# Sen.net
KiCad netlist of a schematic drawn in EAGLE
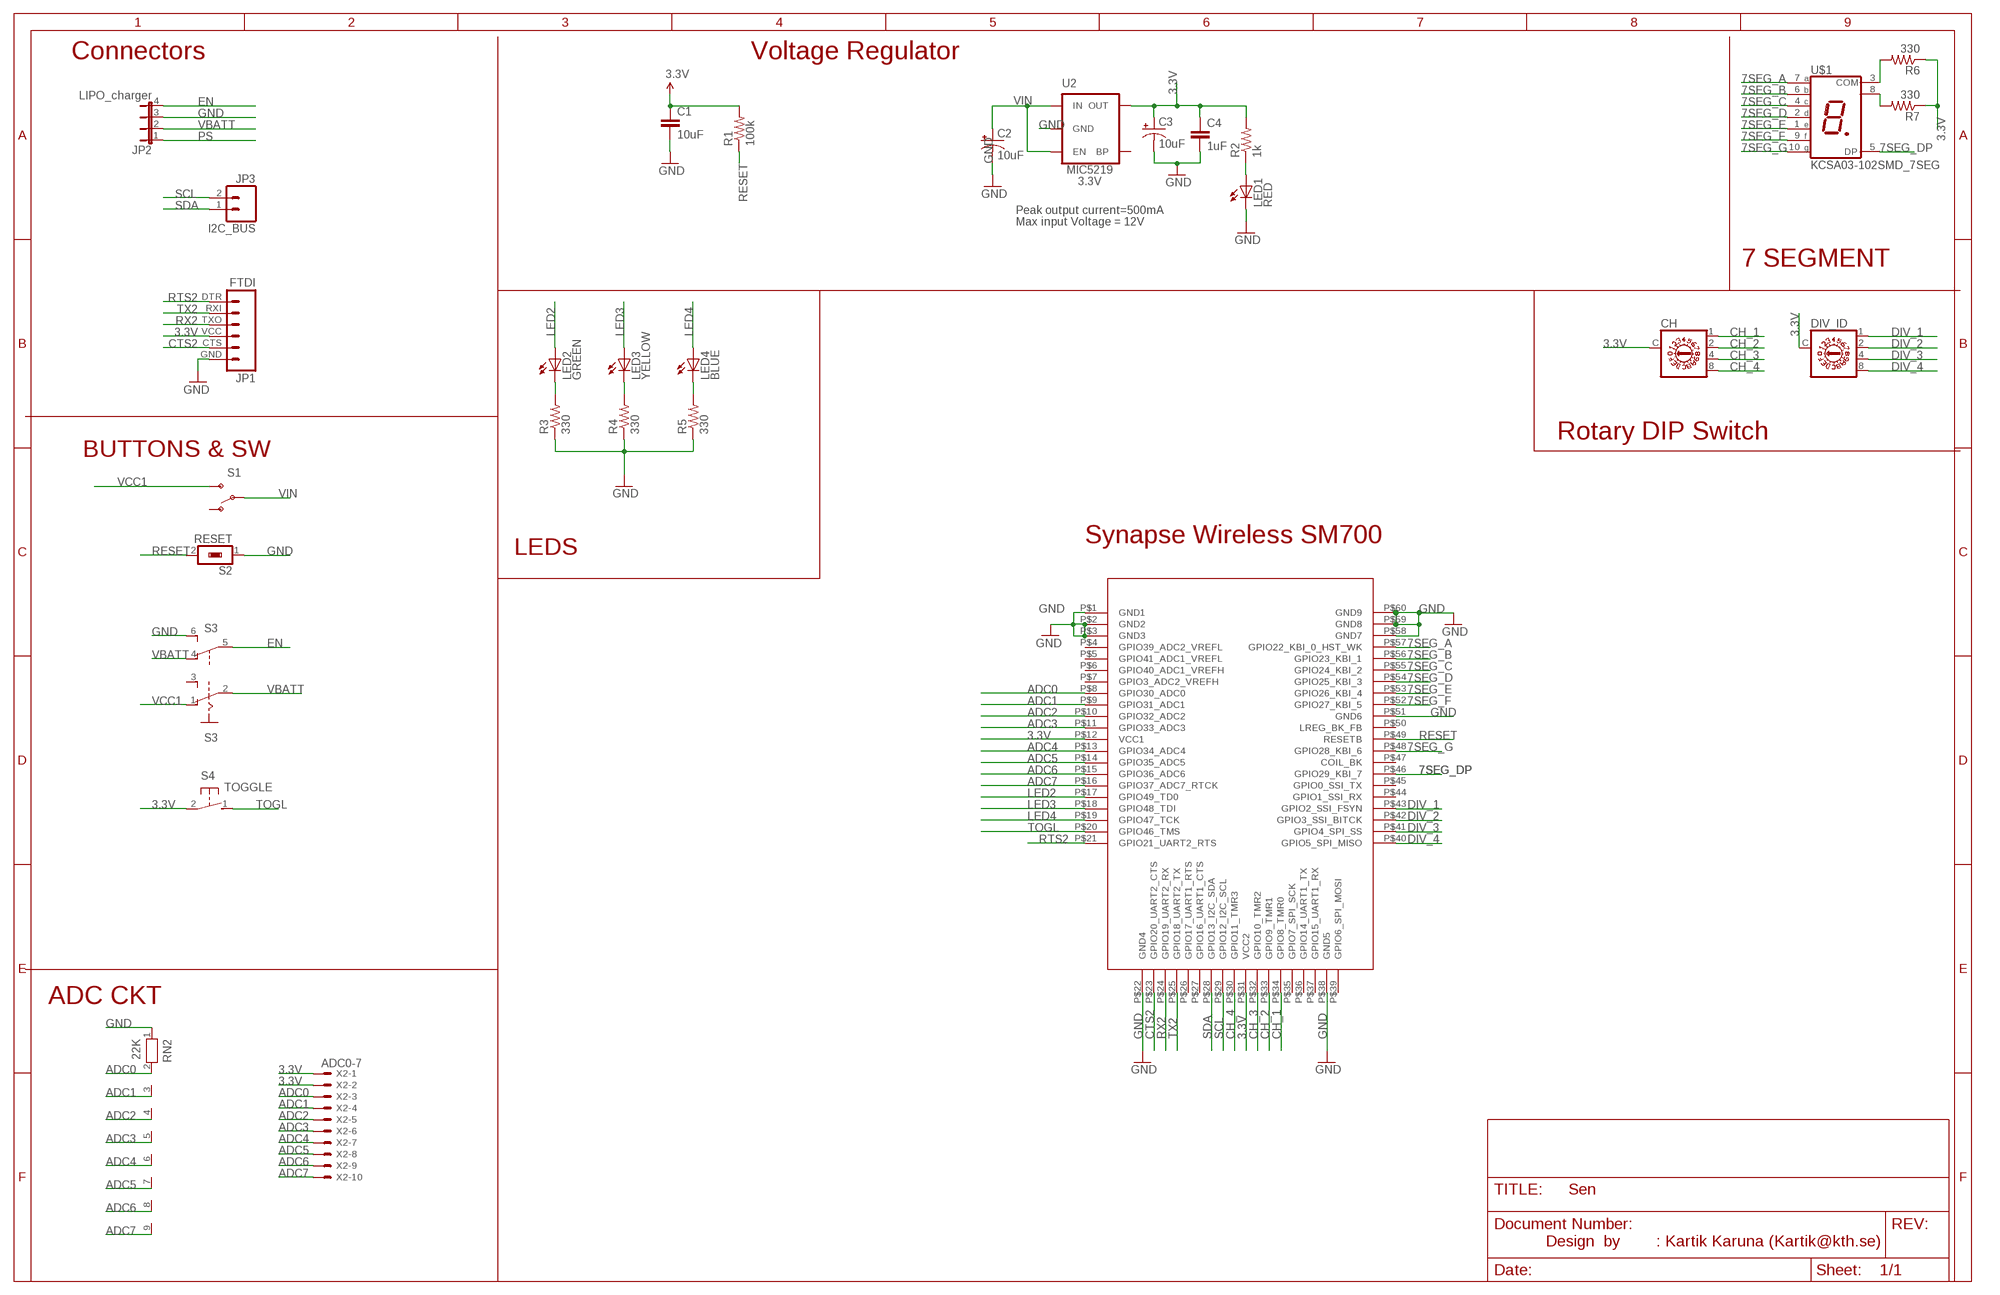
[diagram p0: schematic, sheet 1]

(export (version "E")
  (design (tool "Eeschema 10.0.6"))
  (components
    (comp (ref "C1")
      (value "10uF")
      (footprint "eagle-import:0402-CAP")
      (libsource (lib "eagle-import") (part "CAP0402-CAP"))
    )
    (comp (ref "C2")
      (value "10uF")
      (footprint "eagle-import:EIA3216")
      (libsource (lib "eagle-import") (part "CAP_POL1206"))
    )
    (comp (ref "C3")
      (value "10uF")
      (footprint "eagle-import:EIA3216")
      (libsource (lib "eagle-import") (part "CAP_POL1206"))
    )
    (comp (ref "C4")
      (value "1uF")
      (footprint "eagle-import:0402-CAP")
      (libsource (lib "eagle-import") (part "CAP0402-CAP"))
    )
    (comp (ref "CH")
      (value "A1353HEX")
      (footprint "eagle-import:A1353HEX")
      (libsource (lib "eagle-import") (part "A1353HEX"))
    )
    (comp (ref "DIV_ID")
      (value "A1353HEX")
      (footprint "eagle-import:A1353HEX")
      (libsource (lib "eagle-import") (part "A1353HEX"))
    )
    (comp (ref "JP1")
      (value "FTDI")
      (footprint "eagle-import:FTDI_BASIC")
      (libsource (lib "eagle-import") (part "FTDI_BASICPTH"))
    )
    (comp (ref "JP2")
      (value "LIPO_charger")
      (footprint "eagle-import:JP4")
      (libsource (lib "eagle-import") (part "JP4E"))
    )
    (comp (ref "JP3")
      (value "I2C_BUS")
      (footprint "eagle-import:1X02_NO_SILK")
      (libsource (lib "eagle-import") (part "M021X02_NO_SILK"))
    )
    (comp (ref "LED1")
      (value "RED")
      (footprint "eagle-import:LED-0603")
      (libsource (lib "eagle-import") (part "LED0603"))
    )
    (comp (ref "LED2")
      (value "GREEN")
      (footprint "eagle-import:LED-0603")
      (libsource (lib "eagle-import") (part "LED0603"))
    )
    (comp (ref "LED3")
      (value "YELLOW")
      (footprint "eagle-import:LED-0603")
      (libsource (lib "eagle-import") (part "LED0603"))
    )
    (comp (ref "LED4")
      (value "BLUE")
      (footprint "eagle-import:LED-0603")
      (libsource (lib "eagle-import") (part "LED0603"))
    )
    (comp (ref "R1")
      (value "100k")
      (footprint "eagle-import:0402-RES")
      (libsource (lib "eagle-import") (part "RESISTOR0402-RES"))
    )
    (comp (ref "R2")
      (value "1k")
      (footprint "eagle-import:0402-RES")
      (libsource (lib "eagle-import") (part "RESISTOR0402-RES"))
    )
    (comp (ref "R3")
      (value "330")
      (footprint "eagle-import:0402-RES")
      (libsource (lib "eagle-import") (part "RESISTOR0402-RES"))
    )
    (comp (ref "R4")
      (value "330")
      (footprint "eagle-import:0402-RES")
      (libsource (lib "eagle-import") (part "RESISTOR0402-RES"))
    )
    (comp (ref "R5")
      (value "330")
      (footprint "eagle-import:0402-RES")
      (libsource (lib "eagle-import") (part "RESISTOR0402-RES"))
    )
    (comp (ref "R6")
      (value "330")
      (footprint "eagle-import:0402-RES")
      (libsource (lib "eagle-import") (part "RESISTOR0402-RES"))
    )
    (comp (ref "R7")
      (value "330")
      (footprint "eagle-import:0402-RES")
      (libsource (lib "eagle-import") (part "RESISTOR0402-RES"))
    )
    (comp (ref "RN2")
      (value "22K")
      (footprint "eagle-import:RN-9")
      (libsource (lib "eagle-import") (part "RN08"))
    )
    (comp (ref "S1")
      (value "SWITCH-SPDTSMD")
      (footprint "eagle-import:AYZ0202")
      (libsource (lib "eagle-import") (part "SWITCH-SPDTSMD"))
    )
    (comp (ref "S2")
      (value "RESET")
      (footprint "eagle-import:TYCO_FSM")
      (libsource (lib "eagle-import") (part "TYCO_FSMSFSMSM"))
    )
    (comp (ref "S3")
      (value "A68-A31")
      (footprint "eagle-import:A68-A31")
      (libsource (lib "eagle-import") (part "A68-A31"))
    )
    (comp (ref "S4")
      (value "TOGGLE")
      (footprint "eagle-import:TYCO_FSMRACDA")
      (libsource (lib "eagle-import") (part "TYCO_FSMRACDA"))
    )
    (comp (ref "U$1")
      (value "KCSA03-102SMD_7SEG")
      (footprint "eagle-import:SMD-7SEG")
      (libsource (lib "eagle-import") (part "KCSA03-102SMD_7SEG"))
    )
    (comp (ref "U1")
      (value "SM700PC1SMD")
      (footprint "eagle-import:SYNAPSE_SN700PC1")
      (libsource (lib "eagle-import") (part "SM700PC1SMD"))
    )
    (comp (ref "U2")
      (value "MIC5219")
      (footprint "eagle-import:SOT23-5")
      (libsource (lib "eagle-import") (part "V_REG_LDOSMD"))
    )
    (comp (ref "X2")
      (value "ADC0-7")
      (footprint "eagle-import:53047-10")
      (fields (field (name "MF") "MOLEX") (field (name "MPN") "53047-1010"))
      (libsource (lib "eagle-import") (part "53?-10047"))
    )
  )
  (nets
    (net (code "1") (name "/7SEG_A") (class "Default")
      (node (ref "U$1") (pin "7") (pinfunction "A_7") (pintype "passive"))
      (node (ref "U1") (pin "P$57") (pinfunction "GPIO22_KBI_0_HST_WK_P$57") (pintype "bidirectional"))
    )
    (net (code "2") (name "/7SEG_B") (class "Default")
      (node (ref "U$1") (pin "6") (pinfunction "B_6") (pintype "passive"))
      (node (ref "U1") (pin "P$56") (pinfunction "GPIO23_KBI_1_P$56") (pintype "bidirectional"))
    )
    (net (code "3") (name "/7SEG_C") (class "Default")
      (node (ref "U$1") (pin "4") (pinfunction "C_4") (pintype "passive"))
      (node (ref "U1") (pin "P$55") (pinfunction "GPIO24_KBI_2_P$55") (pintype "bidirectional"))
    )
    (net (code "4") (name "/7SEG_D") (class "Default")
      (node (ref "U$1") (pin "2") (pinfunction "D_2") (pintype "passive"))
      (node (ref "U1") (pin "P$54") (pinfunction "GPIO25_KBI_3_P$54") (pintype "bidirectional"))
    )
    (net (code "5") (name "/7SEG_DP") (class "Default")
      (node (ref "U$1") (pin "5") (pinfunction "DP_5") (pintype "passive"))
      (node (ref "U1") (pin "P$46") (pinfunction "GPIO29_KBI_7_P$46") (pintype "bidirectional"))
    )
    (net (code "6") (name "/7SEG_E") (class "Default")
      (node (ref "U$1") (pin "1") (pinfunction "E_1") (pintype "passive"))
      (node (ref "U1") (pin "P$53") (pinfunction "GPIO26_KBI_4_P$53") (pintype "bidirectional"))
    )
    (net (code "7") (name "/7SEG_F") (class "Default")
      (node (ref "U$1") (pin "9") (pinfunction "F_9") (pintype "passive"))
      (node (ref "U1") (pin "P$52") (pinfunction "GPIO27_KBI_5_P$52") (pintype "bidirectional"))
    )
    (net (code "8") (name "/7SEG_G") (class "Default")
      (node (ref "U$1") (pin "10") (pinfunction "G_10") (pintype "passive"))
      (node (ref "U1") (pin "P$48") (pinfunction "GPIO28_KBI_6_P$48") (pintype "bidirectional"))
    )
    (net (code "9") (name "/ADC0") (class "Default")
      (node (ref "RN2") (pin "2") (pinfunction "2_2") (pintype "passive"))
      (node (ref "U1") (pin "P$8") (pinfunction "GPIO30_ADC0_P$8") (pintype "bidirectional"))
      (node (ref "X2") (pin "3") (pinfunction "S_3") (pintype "passive"))
    )
    (net (code "10") (name "/ADC1") (class "Default")
      (node (ref "RN2") (pin "3") (pinfunction "3_3") (pintype "passive"))
      (node (ref "U1") (pin "P$9") (pinfunction "GPIO31_ADC1_P$9") (pintype "bidirectional"))
      (node (ref "X2") (pin "4") (pinfunction "S_4") (pintype "passive"))
    )
    (net (code "11") (name "/ADC2") (class "Default")
      (node (ref "RN2") (pin "4") (pinfunction "4_4") (pintype "passive"))
      (node (ref "U1") (pin "P$10") (pinfunction "GPIO32_ADC2_P$10") (pintype "bidirectional"))
      (node (ref "X2") (pin "5") (pinfunction "S_5") (pintype "passive"))
    )
    (net (code "12") (name "/ADC3") (class "Default")
      (node (ref "RN2") (pin "5") (pinfunction "5_5") (pintype "passive"))
      (node (ref "U1") (pin "P$11") (pinfunction "GPIO33_ADC3_P$11") (pintype "bidirectional"))
      (node (ref "X2") (pin "6") (pinfunction "S_6") (pintype "passive"))
    )
    (net (code "13") (name "/ADC4") (class "Default")
      (node (ref "RN2") (pin "6") (pinfunction "6_6") (pintype "passive"))
      (node (ref "U1") (pin "P$13") (pinfunction "GPIO34_ADC4_P$13") (pintype "bidirectional"))
      (node (ref "X2") (pin "7") (pinfunction "S_7") (pintype "passive"))
    )
    (net (code "14") (name "/ADC5") (class "Default")
      (node (ref "RN2") (pin "7") (pinfunction "7_7") (pintype "passive"))
      (node (ref "U1") (pin "P$14") (pinfunction "GPIO35_ADC5_P$14") (pintype "bidirectional"))
      (node (ref "X2") (pin "8") (pinfunction "S_8") (pintype "passive"))
    )
    (net (code "15") (name "/ADC6") (class "Default")
      (node (ref "RN2") (pin "8") (pinfunction "8_8") (pintype "passive"))
      (node (ref "U1") (pin "P$15") (pinfunction "GPIO36_ADC6_P$15") (pintype "bidirectional"))
      (node (ref "X2") (pin "9") (pinfunction "S_9") (pintype "passive"))
    )
    (net (code "16") (name "/ADC7") (class "Default")
      (node (ref "RN2") (pin "9") (pinfunction "9_9") (pintype "passive"))
      (node (ref "U1") (pin "P$16") (pinfunction "GPIO37_ADC7_RTCK_P$16") (pintype "bidirectional"))
      (node (ref "X2") (pin "10") (pinfunction "S_10") (pintype "passive"))
    )
    (net (code "17") (name "/CH_1") (class "Default")
      (node (ref "CH") (pin "1") (pinfunction "1_1") (pintype "passive"))
      (node (ref "U1") (pin "P$34") (pinfunction "GPIO8_TMR0_P$34") (pintype "bidirectional"))
    )
    (net (code "18") (name "/CH_2") (class "Default")
      (node (ref "CH") (pin "2") (pinfunction "2_2") (pintype "passive"))
      (node (ref "U1") (pin "P$33") (pinfunction "GPIO9_TMR1_P$33") (pintype "bidirectional"))
    )
    (net (code "19") (name "/CH_3") (class "Default")
      (node (ref "CH") (pin "4") (pinfunction "4_4") (pintype "passive"))
      (node (ref "U1") (pin "P$32") (pinfunction "GPIO10_TMR2_P$32") (pintype "bidirectional"))
    )
    (net (code "20") (name "/CH_4") (class "Default")
      (node (ref "CH") (pin "8") (pinfunction "8_8") (pintype "passive"))
      (node (ref "U1") (pin "P$30") (pinfunction "GPIO11_TMR3_P$30") (pintype "bidirectional"))
    )
    (net (code "21") (name "/CTS2") (class "Default")
      (node (ref "JP1") (pin "CTS") (pinfunction "5_CTS") (pintype "passive"))
      (node (ref "U1") (pin "P$23") (pinfunction "GPIO20_UART2_CTS_P$23") (pintype "bidirectional"))
    )
    (net (code "22") (name "/DIV_1") (class "Default")
      (node (ref "DIV_ID") (pin "1") (pinfunction "1_1") (pintype "passive"))
      (node (ref "U1") (pin "P$43") (pinfunction "GPIO2_SSI_FSYN_P$43") (pintype "bidirectional"))
    )
    (net (code "23") (name "/DIV_2") (class "Default")
      (node (ref "DIV_ID") (pin "2") (pinfunction "2_2") (pintype "passive"))
      (node (ref "U1") (pin "P$42") (pinfunction "GPIO3_SSI_BITCK_P$42") (pintype "bidirectional"))
    )
    (net (code "24") (name "/DIV_3") (class "Default")
      (node (ref "DIV_ID") (pin "4") (pinfunction "4_4") (pintype "passive"))
      (node (ref "U1") (pin "P$41") (pinfunction "GPIO4_SPI_SS_P$41") (pintype "bidirectional"))
    )
    (net (code "25") (name "/DIV_4") (class "Default")
      (node (ref "DIV_ID") (pin "8") (pinfunction "8_8") (pintype "passive"))
      (node (ref "U1") (pin "P$40") (pinfunction "GPIO5_SPI_MISO_P$40") (pintype "bidirectional"))
    )
    (net (code "26") (name "/EN") (class "Default")
      (node (ref "JP2") (pin "4") (pinfunction "4_4") (pintype "passive"))
      (node (ref "S3") (pin "5") (pinfunction "P_5") (pintype "passive"))
    )
    (net (code "27") (name "/LED2") (class "Default")
      (node (ref "LED2") (pin "A") (pinfunction "A_A") (pintype "passive"))
      (node (ref "U1") (pin "P$17") (pinfunction "GPIO49_TD0_P$17") (pintype "bidirectional"))
    )
    (net (code "28") (name "/LED3") (class "Default")
      (node (ref "LED3") (pin "A") (pinfunction "A_A") (pintype "passive"))
      (node (ref "U1") (pin "P$18") (pinfunction "GPIO48_TDI_P$18") (pintype "bidirectional"))
    )
    (net (code "29") (name "/LED4") (class "Default")
      (node (ref "LED4") (pin "A") (pinfunction "A_A") (pintype "passive"))
      (node (ref "U1") (pin "P$19") (pinfunction "GPIO47_TCK_P$19") (pintype "bidirectional"))
    )
    (net (code "30") (name "/PS") (class "Default")
      (node (ref "JP2") (pin "1") (pinfunction "1_1") (pintype "passive"))
    )
    (net (code "31") (name "/RESET") (class "Default")
      (node (ref "R1") (pin "1") (pinfunction "1_1") (pintype "passive"))
      (node (ref "S2") (pin "2") (pinfunction "2_2") (pintype "passive"))
      (node (ref "U1") (pin "P$49") (pinfunction "RESETB_P$49") (pintype "bidirectional"))
    )
    (net (code "32") (name "/RTS2") (class "Default")
      (node (ref "JP1") (pin "DTR") (pinfunction "1_DTR") (pintype "passive"))
      (node (ref "U1") (pin "P$21") (pinfunction "GPIO21_UART2_RTS_P$21") (pintype "bidirectional"))
    )
    (net (code "33") (name "/RX2") (class "Default")
      (node (ref "JP1") (pin "TXO") (pinfunction "3_TXO") (pintype "passive"))
      (node (ref "U1") (pin "P$24") (pinfunction "GPIO19_UART2_RX_P$24") (pintype "bidirectional"))
    )
    (net (code "34") (name "/SCL") (class "Default")
      (node (ref "JP3") (pin "2") (pinfunction "2_2") (pintype "passive"))
      (node (ref "U1") (pin "P$29") (pinfunction "GPIO12_I2C_SCL_P$29") (pintype "bidirectional"))
    )
    (net (code "35") (name "/SDA") (class "Default")
      (node (ref "JP3") (pin "1") (pinfunction "1_1") (pintype "passive"))
      (node (ref "U1") (pin "P$28") (pinfunction "GPIO13_I2C_SDA_P$28") (pintype "bidirectional"))
    )
    (net (code "36") (name "/TOGL") (class "Default")
      (node (ref "S4") (pin "1") (pinfunction "1_1") (pintype "passive"))
      (node (ref "U1") (pin "P$20") (pinfunction "GPIO46_TMS_P$20") (pintype "bidirectional"))
    )
    (net (code "37") (name "/TX2") (class "Default")
      (node (ref "JP1") (pin "RXI") (pinfunction "2_RXI") (pintype "passive"))
      (node (ref "U1") (pin "P$25") (pinfunction "GPIO18_UART2_TX_P$25") (pintype "bidirectional"))
    )
    (net (code "38") (name "/VBATT") (class "Default")
      (node (ref "JP2") (pin "2") (pinfunction "2_2") (pintype "passive"))
      (node (ref "S3") (pin "2") (pinfunction "P_2") (pintype "passive"))
      (node (ref "S3") (pin "4") (pinfunction "O_4") (pintype "passive"))
    )
    (net (code "39") (name "/VCC1") (class "Default")
      (node (ref "S1") (pin "3") (pinfunction "S_3") (pintype "passive"))
      (node (ref "S3") (pin "1") (pinfunction "O_1") (pintype "passive"))
    )
    (net (code "40") (name "/VIN") (class "Default")
      (node (ref "C2") (pin "A") (pinfunction "+_A") (pintype "passive"))
      (node (ref "S1") (pin "2") (pinfunction "P_2") (pintype "passive"))
      (node (ref "U2") (pin "1") (pinfunction "IN_1") (pintype "input"))
      (node (ref "U2") (pin "3") (pinfunction "EN_3") (pintype "input"))
    )
    (net (code "41") (name "3.3V") (class "Default")
      (node (ref "C1") (pin "1") (pinfunction "1_1") (pintype "passive"))
      (node (ref "C3") (pin "A") (pinfunction "+_A") (pintype "passive"))
      (node (ref "C4") (pin "1") (pinfunction "1_1") (pintype "passive"))
      (node (ref "CH") (pin "C") (pinfunction "C_C") (pintype "passive"))
      (node (ref "DIV_ID") (pin "C") (pinfunction "C_C") (pintype "passive"))
      (node (ref "JP1") (pin "VCC") (pinfunction "4_VCC") (pintype "passive"))
      (node (ref "R1") (pin "2") (pinfunction "2_2") (pintype "passive"))
      (node (ref "R2") (pin "2") (pinfunction "2_2") (pintype "passive"))
      (node (ref "R6") (pin "1") (pinfunction "1_1") (pintype "passive"))
      (node (ref "R7") (pin "1") (pinfunction "1_1") (pintype "passive"))
      (node (ref "S4") (pin "2") (pinfunction "2_2") (pintype "passive"))
      (node (ref "U1") (pin "P$12") (pinfunction "VCC1_P$12") (pintype "bidirectional"))
      (node (ref "U1") (pin "P$31") (pinfunction "VCC2_P$31") (pintype "bidirectional"))
      (node (ref "U2") (pin "5") (pinfunction "OUT_5") (pintype "passive"))
      (node (ref "X2") (pin "1") (pinfunction "S_1") (pintype "passive"))
      (node (ref "X2") (pin "2") (pinfunction "S_2") (pintype "passive"))
    )
    (net (code "42") (name "GND") (class "Default")
      (node (ref "C1") (pin "2") (pinfunction "2_2") (pintype "passive"))
      (node (ref "C2") (pin "C") (pinfunction "-_C") (pintype "passive"))
      (node (ref "C3") (pin "C") (pinfunction "-_C") (pintype "passive"))
      (node (ref "C4") (pin "2") (pinfunction "2_2") (pintype "passive"))
      (node (ref "JP1") (pin "GND") (pinfunction "6_GND") (pintype "passive"))
      (node (ref "JP2") (pin "3") (pinfunction "3_3") (pintype "passive"))
      (node (ref "LED1") (pin "C") (pinfunction "C_C") (pintype "passive"))
      (node (ref "R3") (pin "1") (pinfunction "1_1") (pintype "passive"))
      (node (ref "R4") (pin "1") (pinfunction "1_1") (pintype "passive"))
      (node (ref "R5") (pin "1") (pinfunction "1_1") (pintype "passive"))
      (node (ref "RN2") (pin "1") (pinfunction "1_1") (pintype "passive"))
      (node (ref "S2") (pin "1") (pinfunction "1_1") (pintype "passive"))
      (node (ref "S3") (pin "6") (pinfunction "S_6") (pintype "passive"))
      (node (ref "U1") (pin "P$1") (pinfunction "GND1_P$1") (pintype "bidirectional"))
      (node (ref "U1") (pin "P$2") (pinfunction "GND2_P$2") (pintype "bidirectional"))
      (node (ref "U1") (pin "P$22") (pinfunction "GND4_P$22") (pintype "bidirectional"))
      (node (ref "U1") (pin "P$3") (pinfunction "GND3_P$3") (pintype "bidirectional"))
      (node (ref "U1") (pin "P$38") (pinfunction "GND5_P$38") (pintype "bidirectional"))
      (node (ref "U1") (pin "P$51") (pinfunction "GND6_P$51") (pintype "bidirectional"))
      (node (ref "U1") (pin "P$58") (pinfunction "GND7_P$58") (pintype "bidirectional"))
      (node (ref "U1") (pin "P$59") (pinfunction "GND8_P$59") (pintype "bidirectional"))
      (node (ref "U1") (pin "P$60") (pinfunction "GND9_P$60") (pintype "bidirectional"))
      (node (ref "U2") (pin "2") (pinfunction "GND_2") (pintype "input"))
    )
    (net (code "43") (name "Net-(LED1-PadA)") (class "Default")
      (node (ref "LED1") (pin "A") (pinfunction "A_A") (pintype "passive"))
      (node (ref "R2") (pin "1") (pinfunction "1_1") (pintype "passive"))
    )
    (net (code "44") (name "Net-(LED2-PadC)") (class "Default")
      (node (ref "LED2") (pin "C") (pinfunction "C_C") (pintype "passive"))
      (node (ref "R3") (pin "2") (pinfunction "2_2") (pintype "passive"))
    )
    (net (code "45") (name "Net-(LED3-PadC)") (class "Default")
      (node (ref "LED3") (pin "C") (pinfunction "C_C") (pintype "passive"))
      (node (ref "R4") (pin "2") (pinfunction "2_2") (pintype "passive"))
    )
    (net (code "46") (name "Net-(LED4-PadC)") (class "Default")
      (node (ref "LED4") (pin "C") (pinfunction "C_C") (pintype "passive"))
      (node (ref "R5") (pin "2") (pinfunction "2_2") (pintype "passive"))
    )
    (net (code "47") (name "Net-(R6-Pad2)") (class "Default")
      (node (ref "R6") (pin "2") (pinfunction "2_2") (pintype "passive"))
      (node (ref "U$1") (pin "3") (pinfunction "COM_3") (pintype "passive"))
    )
    (net (code "48") (name "Net-(R7-Pad2)") (class "Default")
      (node (ref "R7") (pin "2") (pinfunction "2_2") (pintype "passive"))
      (node (ref "U$1") (pin "8") (pinfunction "COM_8") (pintype "passive"))
    )
    (net (code "49") (name "unconnected-(S1-O-Pad1)") (class "Default")
      (node (ref "S1") (pin "1") (pinfunction "O_1") (pintype "passive"))
    )
    (net (code "50") (name "unconnected-(S3A-S-Pad3)") (class "Default")
      (node (ref "S3") (pin "3") (pinfunction "S_3") (pintype "passive"))
    )
    (net (code "51") (name "unconnected-(U1-COIL_BK-PadP$47)") (class "Default")
      (node (ref "U1") (pin "P$47") (pinfunction "COIL_BK_P$47") (pintype "bidirectional"))
    )
    (net (code "52") (name "unconnected-(U1-GPIO0_SSI_TX-PadP$45)") (class "Default")
      (node (ref "U1") (pin "P$45") (pinfunction "GPIO0_SSI_TX_P$45") (pintype "bidirectional"))
    )
    (net (code "53") (name "unconnected-(U1-GPIO1_SSI_RX-PadP$44)") (class "Default")
      (node (ref "U1") (pin "P$44") (pinfunction "GPIO1_SSI_RX_P$44") (pintype "bidirectional"))
    )
    (net (code "54") (name "unconnected-(U1-GPIO3_ADC2_VREFH-PadP$7)") (class "Default")
      (node (ref "U1") (pin "P$7") (pinfunction "GPIO3_ADC2_VREFH_P$7") (pintype "bidirectional"))
    )
    (net (code "55") (name "unconnected-(U1-GPIO6_SPI_MOSI-PadP$39)") (class "Default")
      (node (ref "U1") (pin "P$39") (pinfunction "GPIO6_SPI_MOSI_P$39") (pintype "bidirectional"))
    )
    (net (code "56") (name "unconnected-(U1-GPIO7_SPI_SCK-PadP$35)") (class "Default")
      (node (ref "U1") (pin "P$35") (pinfunction "GPIO7_SPI_SCK_P$35") (pintype "bidirectional"))
    )
    (net (code "57") (name "unconnected-(U1-GPIO14_UART1_TX-PadP$36)") (class "Default")
      (node (ref "U1") (pin "P$36") (pinfunction "GPIO14_UART1_TX_P$36") (pintype "bidirectional"))
    )
    (net (code "58") (name "unconnected-(U1-GPIO15_UART1_RX-PadP$37)") (class "Default")
      (node (ref "U1") (pin "P$37") (pinfunction "GPIO15_UART1_RX_P$37") (pintype "bidirectional"))
    )
    (net (code "59") (name "unconnected-(U1-GPIO16_UART1_CTS-PadP$27)") (class "Default")
      (node (ref "U1") (pin "P$27") (pinfunction "GPIO16_UART1_CTS_P$27") (pintype "bidirectional"))
    )
    (net (code "60") (name "unconnected-(U1-GPIO17_UART1_RTS-PadP$26)") (class "Default")
      (node (ref "U1") (pin "P$26") (pinfunction "GPIO17_UART1_RTS_P$26") (pintype "bidirectional"))
    )
    (net (code "61") (name "unconnected-(U1-GPIO39_ADC2_VREFL-PadP$4)") (class "Default")
      (node (ref "U1") (pin "P$4") (pinfunction "GPIO39_ADC2_VREFL_P$4") (pintype "bidirectional"))
    )
    (net (code "62") (name "unconnected-(U1-GPIO40_ADC1_VREFH-PadP$6)") (class "Default")
      (node (ref "U1") (pin "P$6") (pinfunction "GPIO40_ADC1_VREFH_P$6") (pintype "bidirectional"))
    )
    (net (code "63") (name "unconnected-(U1-GPIO41_ADC1_VREFL-PadP$5)") (class "Default")
      (node (ref "U1") (pin "P$5") (pinfunction "GPIO41_ADC1_VREFL_P$5") (pintype "bidirectional"))
    )
    (net (code "64") (name "unconnected-(U1-LREG_BK_FB-PadP$50)") (class "Default")
      (node (ref "U1") (pin "P$50") (pinfunction "LREG_BK_FB_P$50") (pintype "bidirectional"))
    )
    (net (code "65") (name "unconnected-(U2-BP-Pad4)") (class "Default")
      (node (ref "U2") (pin "4") (pinfunction "BP_4") (pintype "input"))
    )
  )
)
